# SmartCar_Arduino_V1.net
KiCad netlist of a schematic drawn in EAGLE
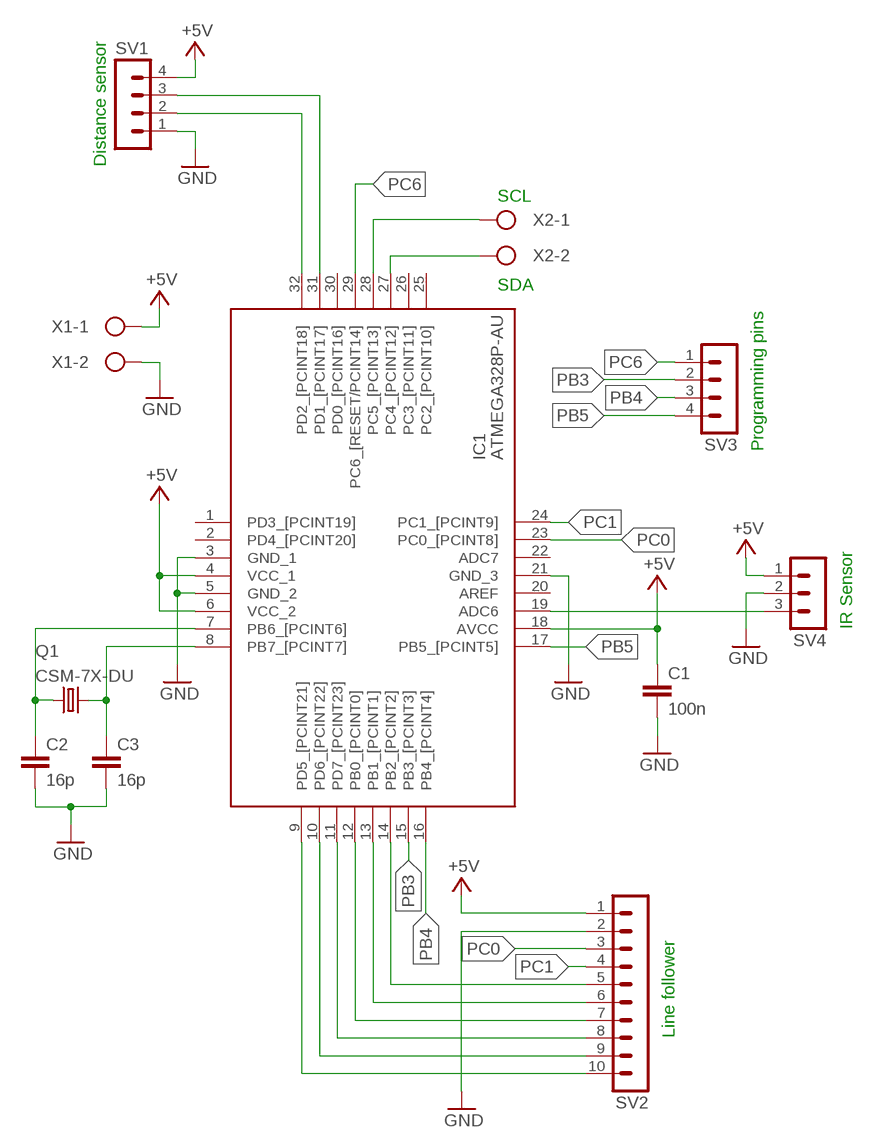
[diagram p0: schematic, sheet 1]

(export (version "E")
  (design (tool "Eeschema 10.0.6"))
  (components
    (comp (ref "C1")
      (value "100n")
      (footprint "eagle-import:C0805")
      (libsource (lib "eagle-import") (part "C-EUC0805"))
    )
    (comp (ref "C2")
      (value "16p")
      (footprint "eagle-import:C0805")
      (libsource (lib "eagle-import") (part "C-EUC0805"))
    )
    (comp (ref "C3")
      (value "16p")
      (footprint "eagle-import:C0805")
      (libsource (lib "eagle-import") (part "C-EUC0805"))
    )
    (comp (ref "IC1")
      (value "ATMEGA328P-AU")
      (footprint "eagle-import:QFP80P900X900X120-32N")
      (fields (field (name "MOUSER_PART_NUMBER") "556-ATMEGA328P-AU"))
      (libsource (lib "eagle-import") (part "ATMEGA328P-AU"))
    )
    (comp (ref "Q1")
      (value "CSM-7X-DU")
      (footprint "eagle-import:CSM-7X-DU")
      (libsource (lib "eagle-import") (part "CSM-7X-DU"))
    )
    (comp (ref "SV1")
      (value "MA04-1")
      (footprint "eagle-import:MA04-1")
      (libsource (lib "eagle-import") (part "MA04-1"))
    )
    (comp (ref "SV2")
      (value "MA10-1")
      (footprint "eagle-import:MA10-1")
      (libsource (lib "eagle-import") (part "MA10-1"))
    )
    (comp (ref "SV3")
      (value "MA04-1")
      (footprint "eagle-import:MA04-1")
      (libsource (lib "eagle-import") (part "MA04-1"))
    )
    (comp (ref "SV4")
      (value "MA03-1")
      (footprint "eagle-import:MA03-1")
      (libsource (lib "eagle-import") (part "MA03-1"))
    )
    (comp (ref "X1")
      (value "W237-102")
      (footprint "eagle-import:W237-102")
      (fields (field (name "MPN") "237-102"))
      (libsource (lib "eagle-import") (part "W237-102"))
    )
    (comp (ref "X2")
      (value "W237-102")
      (footprint "eagle-import:W237-102")
      (fields (field (name "MPN") "237-102"))
      (libsource (lib "eagle-import") (part "W237-102"))
    )
  )
  (nets
    (net (code "1") (name "+5V") (class "Default")
      (node (ref "C1") (pin "1") (pinfunction "1_1") (pintype "passive"))
      (node (ref "IC1") (pin "18") (pinfunction "AVCC_18") (pintype "power_in"))
      (node (ref "IC1") (pin "4") (pinfunction "VCC_1_4") (pintype "power_in"))
      (node (ref "IC1") (pin "6") (pinfunction "VCC_2_6") (pintype "power_in"))
      (node (ref "SV1") (pin "4") (pinfunction "4_4") (pintype "passive"))
      (node (ref "SV2") (pin "1") (pinfunction "1_1") (pintype "passive"))
      (node (ref "SV4") (pin "1") (pinfunction "1_1") (pintype "passive"))
      (node (ref "X1") (pin "1") (pinfunction "KL_1") (pintype "passive"))
    )
    (net (code "2") (name "GND") (class "Default")
      (node (ref "C1") (pin "2") (pinfunction "2_2") (pintype "passive"))
      (node (ref "C2") (pin "2") (pinfunction "2_2") (pintype "passive"))
      (node (ref "C3") (pin "2") (pinfunction "2_2") (pintype "passive"))
      (node (ref "IC1") (pin "21") (pinfunction "GND_3_21") (pintype "power_in"))
      (node (ref "IC1") (pin "3") (pinfunction "GND_1_3") (pintype "power_in"))
      (node (ref "IC1") (pin "5") (pinfunction "GND_2_5") (pintype "power_in"))
      (node (ref "SV1") (pin "1") (pinfunction "1_1") (pintype "passive"))
      (node (ref "SV2") (pin "2") (pinfunction "2_2") (pintype "passive"))
      (node (ref "SV4") (pin "2") (pinfunction "2_2") (pintype "passive"))
      (node (ref "X1") (pin "2") (pinfunction "KL_2") (pintype "passive"))
    )
    (net (code "3") (name "Net-(IC1-ADC6)") (class "Default")
      (node (ref "IC1") (pin "19") (pinfunction "ADC6_19") (pintype "bidirectional"))
      (node (ref "SV4") (pin "3") (pinfunction "3_3") (pintype "passive"))
    )
    (net (code "4") (name "Net-(IC1-PB0_[PCINT0])") (class "Default")
      (node (ref "IC1") (pin "12") (pinfunction "PB0_[PCINT0]_12") (pintype "bidirectional"))
      (node (ref "SV2") (pin "7") (pinfunction "7_7") (pintype "passive"))
    )
    (net (code "5") (name "Net-(IC1-PB1_[PCINT1])") (class "Default")
      (node (ref "IC1") (pin "13") (pinfunction "PB1_[PCINT1]_13") (pintype "bidirectional"))
      (node (ref "SV2") (pin "6") (pinfunction "6_6") (pintype "passive"))
    )
    (net (code "6") (name "Net-(IC1-PB2_[PCINT2])") (class "Default")
      (node (ref "IC1") (pin "14") (pinfunction "PB2_[PCINT2]_14") (pintype "bidirectional"))
      (node (ref "SV2") (pin "5") (pinfunction "5_5") (pintype "passive"))
    )
    (net (code "7") (name "Net-(IC1-PB6_[PCINT6])") (class "Default")
      (node (ref "C2") (pin "1") (pinfunction "1_1") (pintype "passive"))
      (node (ref "IC1") (pin "7") (pinfunction "PB6_[PCINT6]_7") (pintype "bidirectional"))
      (node (ref "Q1") (pin "1") (pinfunction "1_1") (pintype "passive"))
    )
    (net (code "8") (name "Net-(IC1-PB7_[PCINT7])") (class "Default")
      (node (ref "C3") (pin "1") (pinfunction "1_1") (pintype "passive"))
      (node (ref "IC1") (pin "8") (pinfunction "PB7_[PCINT7]_8") (pintype "bidirectional"))
      (node (ref "Q1") (pin "2") (pinfunction "2_2") (pintype "passive"))
    )
    (net (code "9") (name "Net-(IC1-PC4_[PCINT12])") (class "Default")
      (node (ref "IC1") (pin "27") (pinfunction "PC4_[PCINT12]_27") (pintype "bidirectional"))
      (node (ref "X2") (pin "2") (pinfunction "KL_2") (pintype "passive"))
    )
    (net (code "10") (name "Net-(IC1-PC5_[PCINT13])") (class "Default")
      (node (ref "IC1") (pin "28") (pinfunction "PC5_[PCINT13]_28") (pintype "bidirectional"))
      (node (ref "X2") (pin "1") (pinfunction "KL_1") (pintype "passive"))
    )
    (net (code "11") (name "Net-(IC1-PD1_[PCINT17])") (class "Default")
      (node (ref "IC1") (pin "31") (pinfunction "PD1_[PCINT17]_31") (pintype "bidirectional"))
      (node (ref "SV1") (pin "3") (pinfunction "3_3") (pintype "passive"))
    )
    (net (code "12") (name "Net-(IC1-PD2_[PCINT18])") (class "Default")
      (node (ref "IC1") (pin "32") (pinfunction "PD2_[PCINT18]_32") (pintype "bidirectional"))
      (node (ref "SV1") (pin "2") (pinfunction "2_2") (pintype "passive"))
    )
    (net (code "13") (name "Net-(IC1-PD5_[PCINT21])") (class "Default")
      (node (ref "IC1") (pin "9") (pinfunction "PD5_[PCINT21]_9") (pintype "bidirectional"))
      (node (ref "SV2") (pin "10") (pinfunction "10_10") (pintype "passive"))
    )
    (net (code "14") (name "Net-(IC1-PD6_[PCINT22])") (class "Default")
      (node (ref "IC1") (pin "10") (pinfunction "PD6_[PCINT22]_10") (pintype "bidirectional"))
      (node (ref "SV2") (pin "9") (pinfunction "9_9") (pintype "passive"))
    )
    (net (code "15") (name "Net-(IC1-PD7_[PCINT23])") (class "Default")
      (node (ref "IC1") (pin "11") (pinfunction "PD7_[PCINT23]_11") (pintype "bidirectional"))
      (node (ref "SV2") (pin "8") (pinfunction "8_8") (pintype "passive"))
    )
    (net (code "16") (name "PB3") (class "Default")
      (node (ref "IC1") (pin "15") (pinfunction "PB3_[PCINT3]_15") (pintype "bidirectional"))
      (node (ref "SV3") (pin "2") (pinfunction "2_2") (pintype "passive"))
    )
    (net (code "17") (name "PB4") (class "Default")
      (node (ref "IC1") (pin "16") (pinfunction "PB4_[PCINT4]_16") (pintype "bidirectional"))
      (node (ref "SV3") (pin "3") (pinfunction "3_3") (pintype "passive"))
    )
    (net (code "18") (name "PB5") (class "Default")
      (node (ref "IC1") (pin "17") (pinfunction "PB5_[PCINT5]_17") (pintype "bidirectional"))
      (node (ref "SV3") (pin "4") (pinfunction "4_4") (pintype "passive"))
    )
    (net (code "19") (name "PC0") (class "Default")
      (node (ref "IC1") (pin "23") (pinfunction "PC0_[PCINT8]_23") (pintype "bidirectional"))
      (node (ref "SV2") (pin "3") (pinfunction "3_3") (pintype "passive"))
    )
    (net (code "20") (name "PC1") (class "Default")
      (node (ref "IC1") (pin "24") (pinfunction "PC1_[PCINT9]_24") (pintype "bidirectional"))
      (node (ref "SV2") (pin "4") (pinfunction "4_4") (pintype "passive"))
    )
    (net (code "21") (name "PC6") (class "Default")
      (node (ref "IC1") (pin "29") (pinfunction "PC6_[RESET/PCINT14]_29") (pintype "bidirectional"))
      (node (ref "SV3") (pin "1") (pinfunction "1_1") (pintype "passive"))
    )
    (net (code "22") (name "unconnected-(IC1-ADC7-Pad22)") (class "Default")
      (node (ref "IC1") (pin "22") (pinfunction "ADC7_22") (pintype "bidirectional"))
    )
    (net (code "23") (name "unconnected-(IC1-AREF-Pad20)") (class "Default")
      (node (ref "IC1") (pin "20") (pinfunction "AREF_20") (pintype "bidirectional"))
    )
    (net (code "24") (name "unconnected-(IC1-PC2_[PCINT10]-Pad25)") (class "Default")
      (node (ref "IC1") (pin "25") (pinfunction "PC2_[PCINT10]_25") (pintype "bidirectional"))
    )
    (net (code "25") (name "unconnected-(IC1-PC3_[PCINT11]-Pad26)") (class "Default")
      (node (ref "IC1") (pin "26") (pinfunction "PC3_[PCINT11]_26") (pintype "bidirectional"))
    )
    (net (code "26") (name "unconnected-(IC1-PD0_[PCINT16]-Pad30)") (class "Default")
      (node (ref "IC1") (pin "30") (pinfunction "PD0_[PCINT16]_30") (pintype "bidirectional"))
    )
    (net (code "27") (name "unconnected-(IC1-PD3_[PCINT19]-Pad1)") (class "Default")
      (node (ref "IC1") (pin "1") (pinfunction "PD3_[PCINT19]_1") (pintype "bidirectional"))
    )
    (net (code "28") (name "unconnected-(IC1-PD4_[PCINT20]-Pad2)") (class "Default")
      (node (ref "IC1") (pin "2") (pinfunction "PD4_[PCINT20]_2") (pintype "bidirectional"))
    )
  )
)
